# demo3.net
KiCad netlist of a schematic drawn in EAGLE
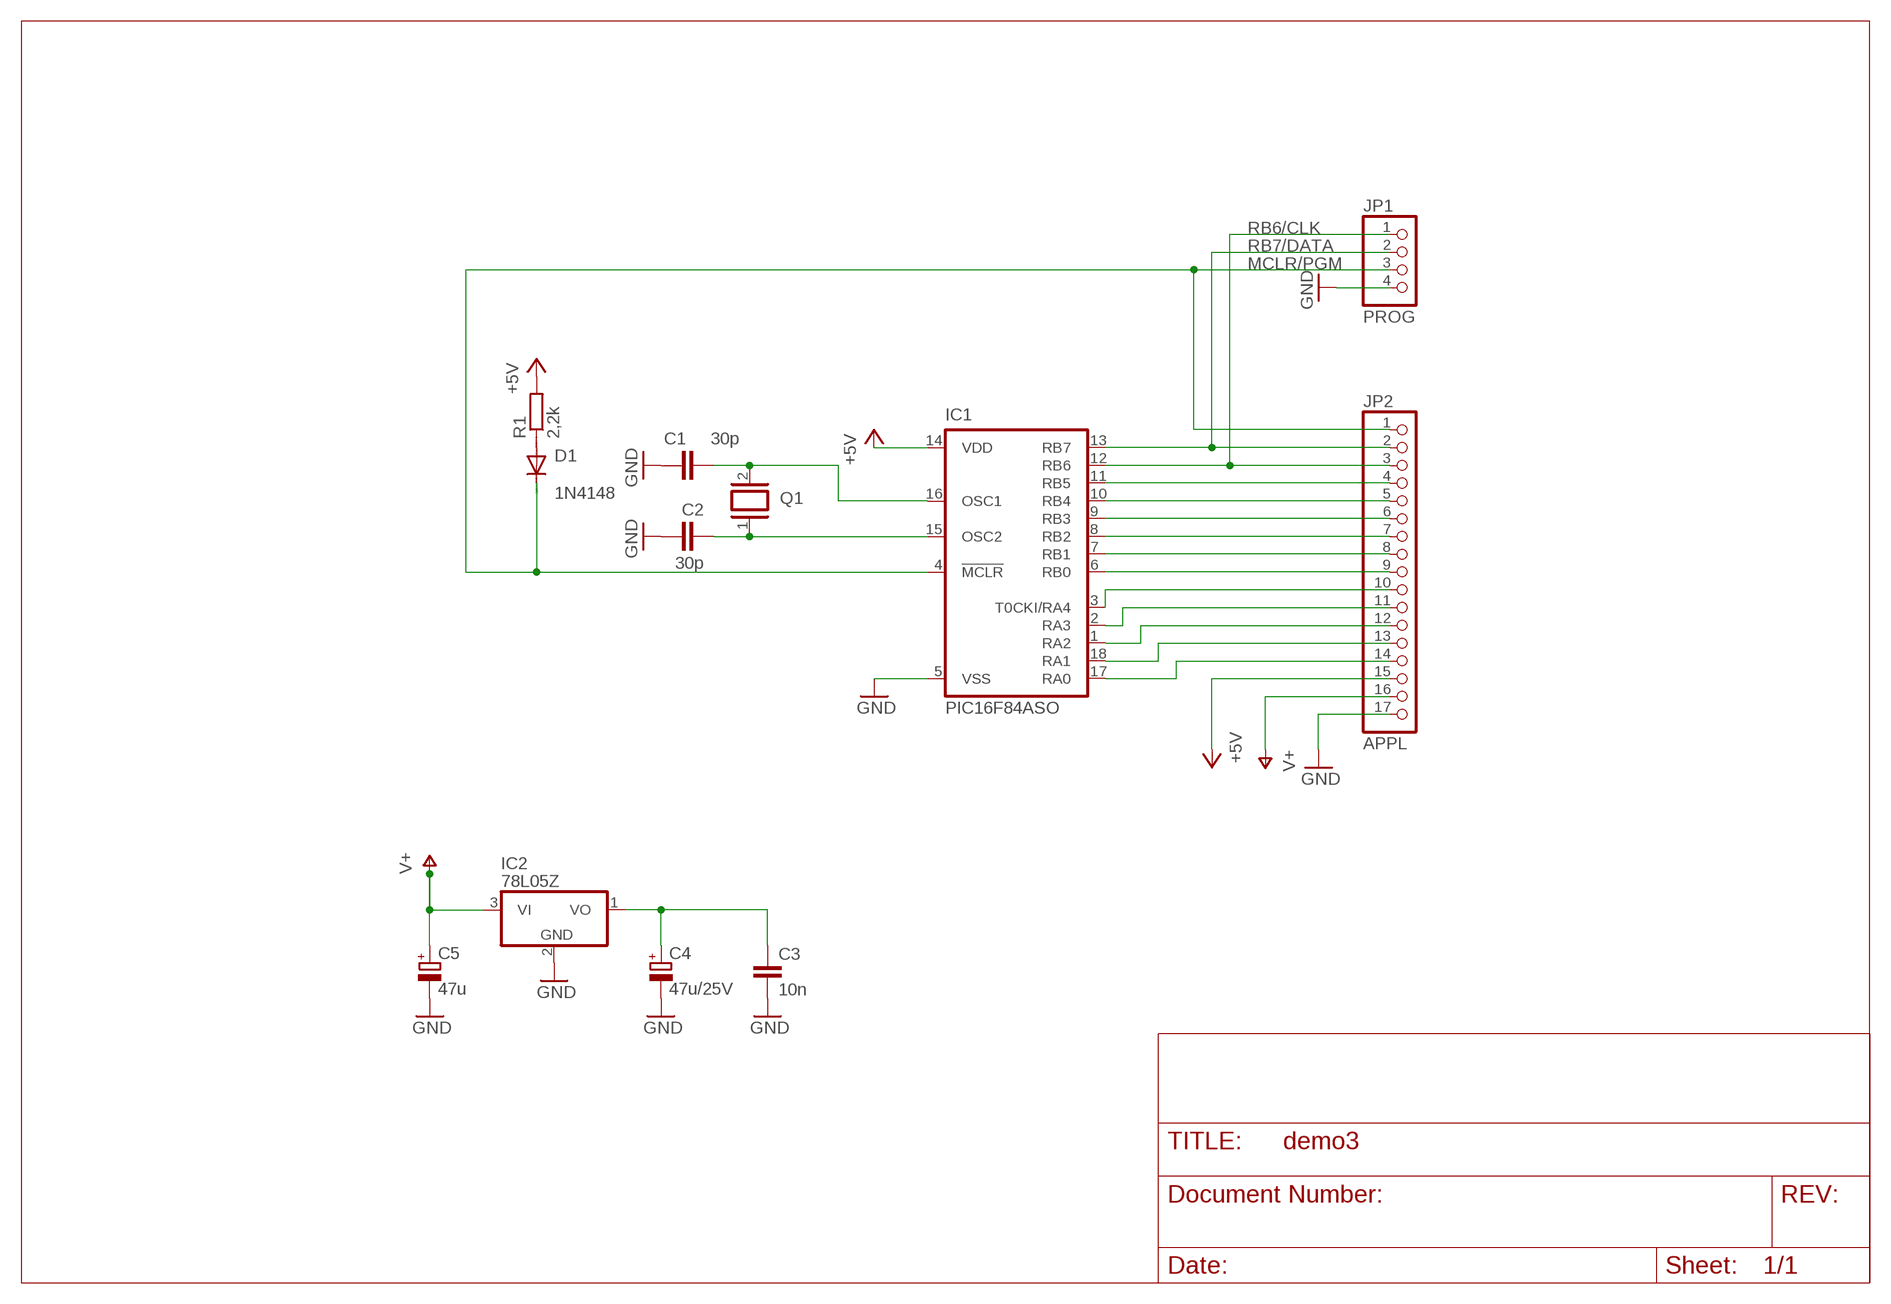
[diagram p0: schematic, sheet 1]

(export (version "E")
  (design (tool "Eeschema 10.0.6"))
  (components
    (comp (ref "C1")
      (value "30p")
      (footprint "eagle-import:C1206")
      (libsource (lib "eagle-import") (part "C-EUC1206"))
    )
    (comp (ref "C2")
      (value "30p")
      (footprint "eagle-import:C1206")
      (libsource (lib "eagle-import") (part "C-EUC1206"))
    )
    (comp (ref "C3")
      (value "10n")
      (footprint "eagle-import:C025-025X050")
      (libsource (lib "eagle-import") (part "C-EU025-025X050"))
    )
    (comp (ref "C4")
      (value "47u/25V")
      (footprint "eagle-import:TAP5-45")
      (libsource (lib "eagle-import") (part "CPOL-EUTAP5-45"))
    )
    (comp (ref "C5")
      (value "47u")
      (footprint "eagle-import:TAP5-45")
      (libsource (lib "eagle-import") (part "CPOL-EUTAP5-45"))
    )
    (comp (ref "D1")
      (value "1N4148")
      (footprint "eagle-import:DO35-10")
      (libsource (lib "eagle-import") (part "1N4148DO35-10"))
    )
    (comp (ref "IC1")
      (value "PIC16F84ASO")
      (footprint "eagle-import:SO-18W")
      (fields (field (name "MF") "MICROCHIP") (field (name "MPN") "PIC16F84A-04/SO"))
      (libsource (lib "eagle-import") (part "PIC16F8SO4A"))
    )
    (comp (ref "IC2")
      (value "78L05Z")
      (footprint "eagle-import:TO92")
      (libsource (lib "eagle-import") (part "78ZL05"))
    )
    (comp (ref "JP1")
      (value "PROG")
      (footprint "eagle-import:1X04")
      (libsource (lib "eagle-import") (part "PINHD-1X4"))
    )
    (comp (ref "JP2")
      (value "APPL")
      (footprint "eagle-import:1X17")
      (libsource (lib "eagle-import") (part "PINHD-1X17"))
    )
    (comp (ref "Q1")
      (value "XTAL/S")
      (footprint "eagle-import:QS")
      (libsource (lib "eagle-import") (part "XTAL/S"))
    )
    (comp (ref "R1")
      (value "2,2k")
      (footprint "eagle-import:R1206")
      (libsource (lib "eagle-import") (part "R-EU_R1206"))
    )
  )
  (nets
    (net (code "1") (name "+5V") (class "Default")
      (node (ref "IC1") (pin "14") (pinfunction "VDD_14") (pintype "power_in"))
      (node (ref "JP2") (pin "15") (pinfunction "15_15") (pintype "passive"))
      (node (ref "R1") (pin "2") (pinfunction "2_2") (pintype "passive"))
    )
    (net (code "2") (name "/MCLR{slash}PGM") (class "Default")
      (node (ref "D1") (pin "C") (pinfunction "C_C") (pintype "passive"))
      (node (ref "IC1") (pin "4") (pinfunction "~{MCLR}_4") (pintype "input"))
      (node (ref "JP1") (pin "3") (pinfunction "3_3") (pintype "passive"))
      (node (ref "JP2") (pin "1") (pinfunction "1_1") (pintype "passive"))
    )
    (net (code "3") (name "/RB6{slash}CLK") (class "Default")
      (node (ref "IC1") (pin "12") (pinfunction "RB6_12") (pintype "bidirectional"))
      (node (ref "JP1") (pin "1") (pinfunction "1_1") (pintype "passive"))
      (node (ref "JP2") (pin "3") (pinfunction "3_3") (pintype "passive"))
    )
    (net (code "4") (name "/RB7{slash}DATA") (class "Default")
      (node (ref "IC1") (pin "13") (pinfunction "RB7_13") (pintype "bidirectional"))
      (node (ref "JP1") (pin "2") (pinfunction "2_2") (pintype "passive"))
      (node (ref "JP2") (pin "2") (pinfunction "2_2") (pintype "passive"))
    )
    (net (code "5") (name "GND") (class "Default")
      (node (ref "C1") (pin "1") (pinfunction "1_1") (pintype "passive"))
      (node (ref "C2") (pin "1") (pinfunction "1_1") (pintype "passive"))
      (node (ref "C3") (pin "2") (pinfunction "2_2") (pintype "passive"))
      (node (ref "C4") (pin "-") (pinfunction "-_-") (pintype "passive"))
      (node (ref "C5") (pin "-") (pinfunction "-_-") (pintype "passive"))
      (node (ref "IC1") (pin "5") (pinfunction "VSS_5") (pintype "power_in"))
      (node (ref "IC2") (pin "2") (pinfunction "GND_2") (pintype "passive"))
      (node (ref "JP1") (pin "4") (pinfunction "4_4") (pintype "passive"))
      (node (ref "JP2") (pin "17") (pinfunction "17_17") (pintype "passive"))
    )
    (net (code "6") (name "Net-(D1-PadA)") (class "Default")
      (node (ref "D1") (pin "A") (pinfunction "A_A") (pintype "passive"))
      (node (ref "R1") (pin "1") (pinfunction "1_1") (pintype "passive"))
    )
    (net (code "7") (name "Net-(IC1-OSC1)") (class "Default")
      (node (ref "C1") (pin "2") (pinfunction "2_2") (pintype "passive"))
      (node (ref "IC1") (pin "16") (pinfunction "OSC1_16") (pintype "input"))
      (node (ref "Q1") (pin "2") (pinfunction "2_2") (pintype "passive"))
    )
    (net (code "8") (name "Net-(IC1-OSC2)") (class "Default")
      (node (ref "C2") (pin "2") (pinfunction "2_2") (pintype "passive"))
      (node (ref "IC1") (pin "15") (pinfunction "OSC2_15") (pintype "output"))
      (node (ref "Q1") (pin "1") (pinfunction "1_1") (pintype "passive"))
    )
    (net (code "9") (name "Net-(IC1-RA0)") (class "Default")
      (node (ref "IC1") (pin "17") (pinfunction "RA0_17") (pintype "bidirectional"))
      (node (ref "JP2") (pin "14") (pinfunction "14_14") (pintype "passive"))
    )
    (net (code "10") (name "Net-(IC1-RA1)") (class "Default")
      (node (ref "IC1") (pin "18") (pinfunction "RA1_18") (pintype "bidirectional"))
      (node (ref "JP2") (pin "13") (pinfunction "13_13") (pintype "passive"))
    )
    (net (code "11") (name "Net-(IC1-RA2)") (class "Default")
      (node (ref "IC1") (pin "1") (pinfunction "RA2_1") (pintype "bidirectional"))
      (node (ref "JP2") (pin "12") (pinfunction "12_12") (pintype "passive"))
    )
    (net (code "12") (name "Net-(IC1-RA3)") (class "Default")
      (node (ref "IC1") (pin "2") (pinfunction "RA3_2") (pintype "bidirectional"))
      (node (ref "JP2") (pin "11") (pinfunction "11_11") (pintype "passive"))
    )
    (net (code "13") (name "Net-(IC1-RB0)") (class "Default")
      (node (ref "IC1") (pin "6") (pinfunction "RB0_6") (pintype "bidirectional"))
      (node (ref "JP2") (pin "9") (pinfunction "9_9") (pintype "passive"))
    )
    (net (code "14") (name "Net-(IC1-RB1)") (class "Default")
      (node (ref "IC1") (pin "7") (pinfunction "RB1_7") (pintype "bidirectional"))
      (node (ref "JP2") (pin "8") (pinfunction "8_8") (pintype "passive"))
    )
    (net (code "15") (name "Net-(IC1-RB2)") (class "Default")
      (node (ref "IC1") (pin "8") (pinfunction "RB2_8") (pintype "bidirectional"))
      (node (ref "JP2") (pin "7") (pinfunction "7_7") (pintype "passive"))
    )
    (net (code "16") (name "Net-(IC1-RB3)") (class "Default")
      (node (ref "IC1") (pin "9") (pinfunction "RB3_9") (pintype "bidirectional"))
      (node (ref "JP2") (pin "6") (pinfunction "6_6") (pintype "passive"))
    )
    (net (code "17") (name "Net-(IC1-RB4)") (class "Default")
      (node (ref "IC1") (pin "10") (pinfunction "RB4_10") (pintype "bidirectional"))
      (node (ref "JP2") (pin "5") (pinfunction "5_5") (pintype "passive"))
    )
    (net (code "18") (name "Net-(IC1-RB5)") (class "Default")
      (node (ref "IC1") (pin "11") (pinfunction "RB5_11") (pintype "bidirectional"))
      (node (ref "JP2") (pin "4") (pinfunction "4_4") (pintype "passive"))
    )
    (net (code "19") (name "Net-(IC1-T0CKI{slash}RA4)") (class "Default")
      (node (ref "IC1") (pin "3") (pinfunction "T0CKI/RA4_3") (pintype "bidirectional"))
      (node (ref "JP2") (pin "10") (pinfunction "10_10") (pintype "passive"))
    )
    (net (code "20") (name "Net-(IC2-VO)") (class "Default")
      (node (ref "C3") (pin "1") (pinfunction "1_1") (pintype "passive"))
      (node (ref "C4") (pin "+") (pinfunction "+_+") (pintype "passive"))
      (node (ref "IC2") (pin "1") (pinfunction "VO_1") (pintype "passive"))
    )
    (net (code "21") (name "V+") (class "Default")
      (node (ref "C5") (pin "+") (pinfunction "+_+") (pintype "passive"))
      (node (ref "IC2") (pin "3") (pinfunction "VI_3") (pintype "input"))
      (node (ref "JP2") (pin "16") (pinfunction "16_16") (pintype "passive"))
    )
  )
)
